# USBandPOWER.net
KiCad netlist of a schematic drawn in Altium Designer
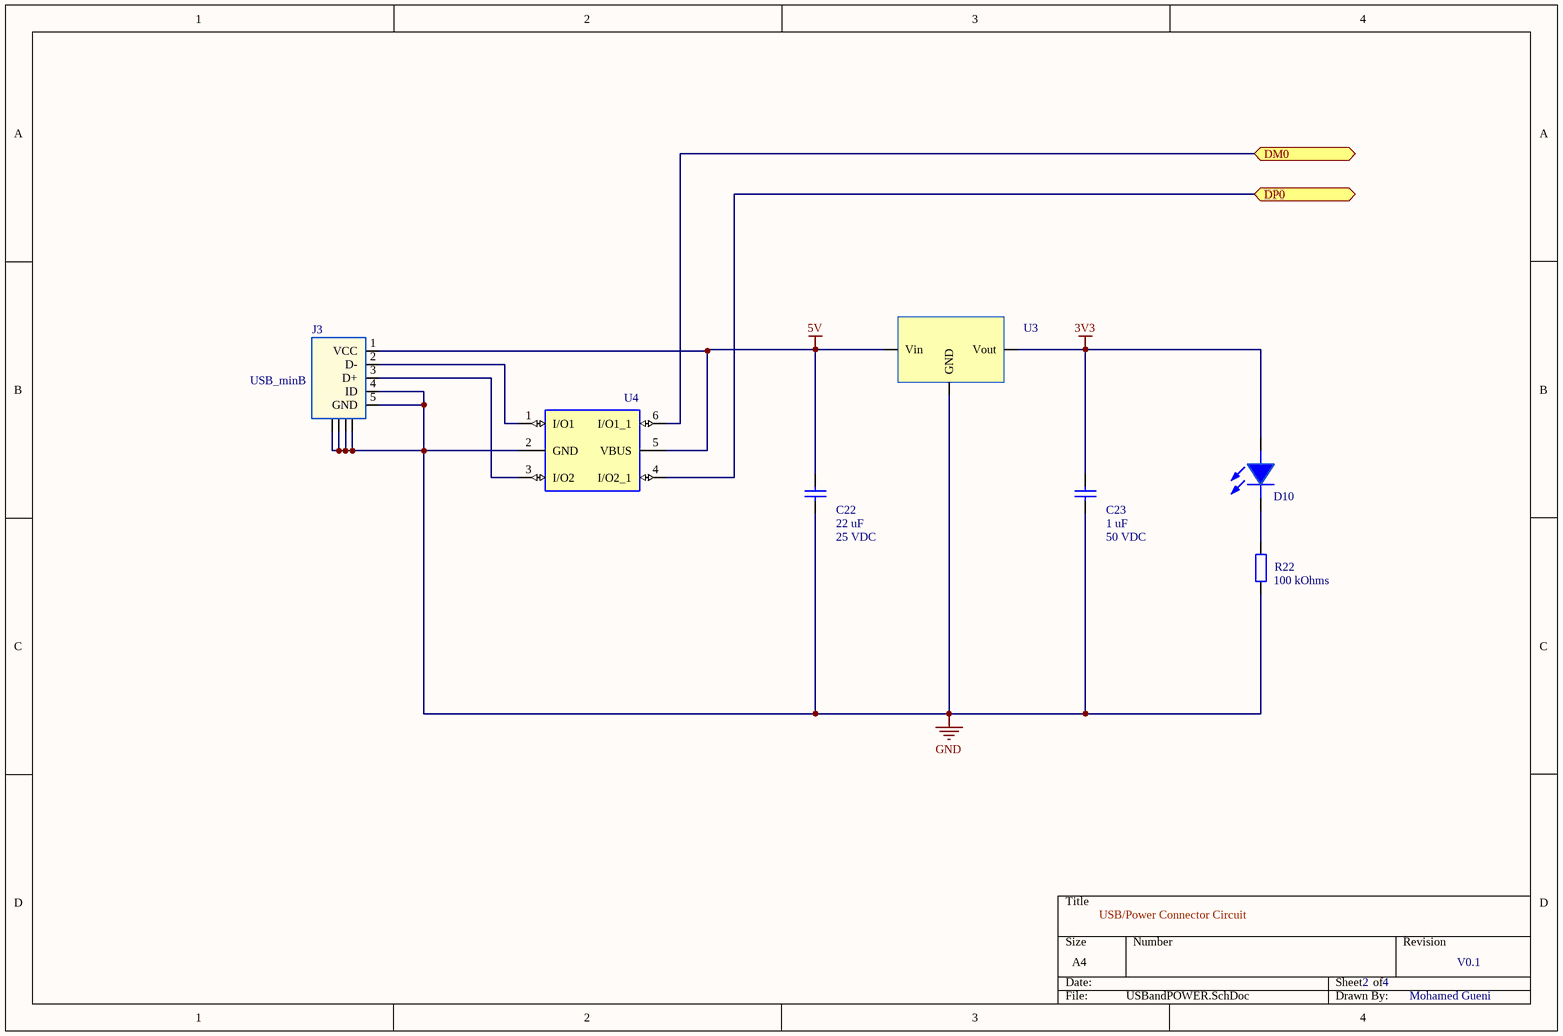
[diagram p0: USBandPOWER.SchDoc]

(export (version "E")
  (design (tool "Eeschema 10.0.6"))
  (components
    (comp (ref "C22")
      (value "Capacitor")
      (footprint "CAP-1210")
      (fields
        (field (name "VALUE 1") "22 uF")
        (field (name "VALUE 2") "25 VDC")
        (field (name "PART NUMBER") "C-000000004")
      )
      (libsource (lib "DATABASE") (part "Capacitor"))
    )
    (comp (ref "C23")
      (value "Capacitor")
      (footprint "CAP-1210")
      (fields
        (field (name "VALUE 1") "1 uF")
        (field (name "VALUE 2") "50 VDC")
        (field (name "PART NUMBER") "C-000000005")
      )
      (libsource (lib "DATABASE") (part "Capacitor"))
    )
    (comp (ref "D10")
      (value "SML-H12U8TT86C")
      (footprint "LEDC2012X90N")
      (libsource (lib "DATABASE") (part "LED"))
    )
    (comp (ref "J3")
      (value "USB_minB")
      (footprint "XM7D-0512")
      (fields (field (name "PART NUMBER") "J-000000003"))
      (libsource (lib "DATABASE") (part "USB_minB"))
    )
    (comp (ref "R22")
      (value "Resistor")
      (footprint "R0603")
      (fields (field (name "VALUE 1") "100 kOhms") (field (name "PART NUMBER") "R-000000002"))
      (libsource (lib "DATABASE") (part "Resistor"))
    )
    (comp (ref "U3")
      (value "Voltage Regulator")
      (footprint "REG-SOT230P700X180-4N")
      (fields (field (name "PART NUMBER") "U-000000004"))
      (libsource (lib "DATABASE") (part "Voltage Regulator"))
    )
    (comp (ref "U4")
      (value "USBLC6-2SC6")
      (footprint "SOT95P280X145")
      (fields (field (name "PART NUMBER") "U-000000006"))
      (libsource (lib "DATABASE") (part "USBLC6-2SC6"))
    )
  )
  (nets
    (net (code "1") (name "/DM0") (class "Default")
      (node (ref "U4") (pin "6") (pinfunction "I/O1_1_6") (pintype "bidirectional"))
    )
    (net (code "2") (name "/DP0") (class "Default")
      (node (ref "U4") (pin "4") (pinfunction "I/O2_1_4") (pintype "bidirectional"))
    )
    (net (code "3") (name "3V3") (class "Default")
      (node (ref "C23") (pin "2") (pinfunction "2_2") (pintype "passive"))
      (node (ref "D10") (pin "2") (pinfunction "A_2") (pintype "passive"))
      (node (ref "U3") (pin "3") (pinfunction "Vout_3") (pintype "passive"))
    )
    (net (code "4") (name "5V") (class "Default")
      (node (ref "C22") (pin "2") (pinfunction "2_2") (pintype "passive"))
      (node (ref "J3") (pin "1") (pinfunction "VCC_1") (pintype "power_in"))
      (node (ref "U3") (pin "2") (pinfunction "Vin_2") (pintype "passive"))
      (node (ref "U4") (pin "5") (pinfunction "VBUS_5") (pintype "passive"))
    )
    (net (code "5") (name "GND") (class "Default")
      (node (ref "C22") (pin "1") (pinfunction "1_1") (pintype "passive"))
      (node (ref "C23") (pin "1") (pinfunction "1_1") (pintype "passive"))
      (node (ref "J3") (pin "4") (pinfunction "ID_4") (pintype "power_in"))
      (node (ref "J3") (pin "5") (pinfunction "GND_5") (pintype "power_in"))
      (node (ref "J3") (pin "SH1") (pinfunction "SHIELD_SH1") (pintype "power_in"))
      (node (ref "R22") (pin "1") (pinfunction "1_1") (pintype "passive"))
      (node (ref "U3") (pin "1") (pinfunction "GND_1") (pintype "passive"))
      (node (ref "U4") (pin "2") (pinfunction "GND_2") (pintype "passive"))
    )
    (net (code "6") (name "Net-(D10-K)") (class "Default")
      (node (ref "D10") (pin "1") (pinfunction "K_1") (pintype "passive"))
      (node (ref "R22") (pin "2") (pinfunction "2_2") (pintype "passive"))
    )
    (net (code "7") (name "Net-(J3-D+)") (class "Default")
      (node (ref "J3") (pin "3") (pinfunction "D+_3") (pintype "bidirectional"))
      (node (ref "U4") (pin "3") (pinfunction "I/O2_3") (pintype "bidirectional"))
    )
    (net (code "8") (name "Net-(J3-D-)") (class "Default")
      (node (ref "J3") (pin "2") (pinfunction "D-_2") (pintype "bidirectional"))
      (node (ref "U4") (pin "1") (pinfunction "I/O1_1") (pintype "bidirectional"))
    )
  )
)
